# V_1.net
KiCad netlist of a schematic drawn in Altium Designer
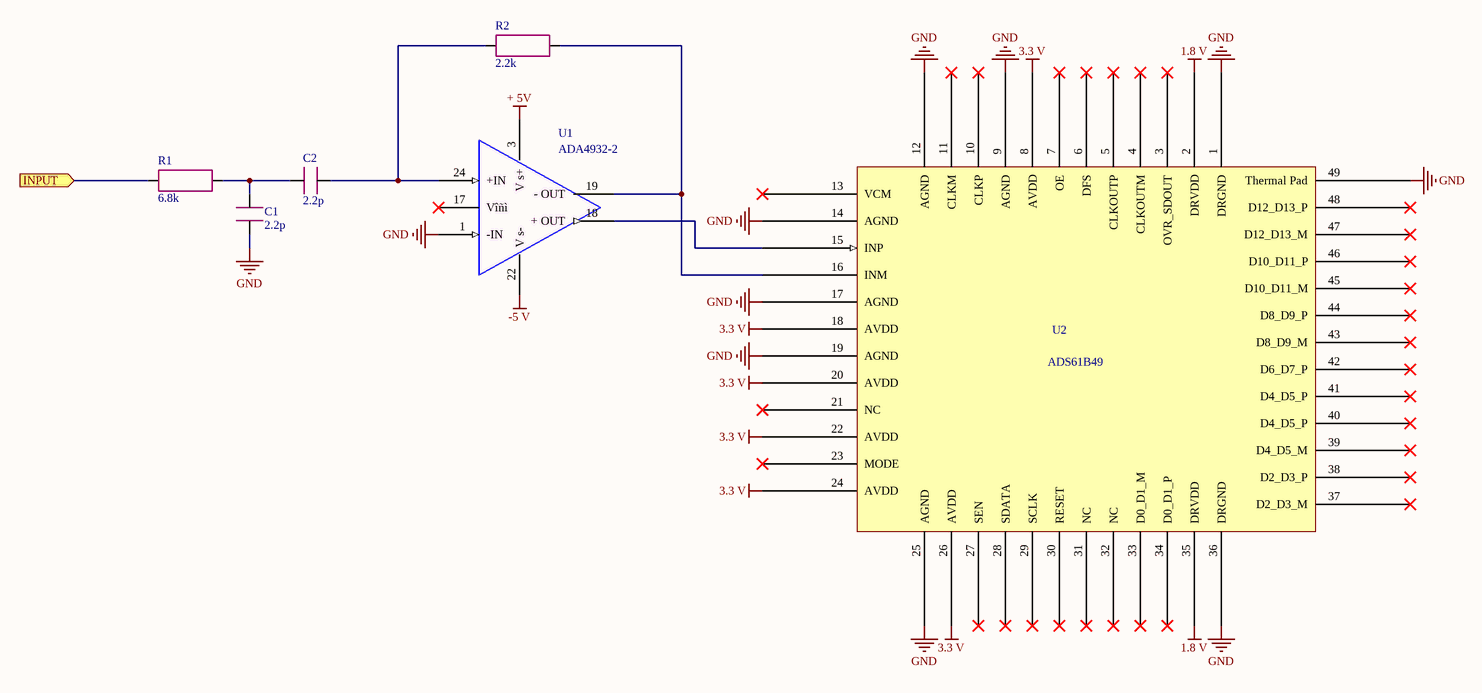
[diagram p0: V_1.SchDoc]

(export (version "E")
  (design (tool "Eeschema 10.0.6"))
  (components
    (comp (ref "C1") (value "2.2p") (footprint "V_1:C_0805") (libsource (lib "V_1") (part "C")))
    (comp (ref "C2") (value "2.2p") (footprint "V_1:C_0805") (libsource (lib "V_1") (part "C")))
    (comp (ref "R1") (value "6.8k") (footprint "V_1:R_0805") (libsource (lib "V_1") (part "R")))
    (comp (ref "R2") (value "2.2k") (footprint "V_1:R_0805") (libsource (lib "V_1") (part "R")))
    (comp (ref "U1")
      (value "ADA4932-2")
      (footprint "V_1:ADA4932-2")
      (libsource (lib "V_1") (part "ADA4932-2"))
    )
    (comp (ref "U2") (value "ADS61B49") (footprint "V_1:ADS61B49") (libsource (lib "V_1") (part "ADS61B49")))
  )
  (nets
    (net (code "1") (name "+ 5V") (class "Default")
      (node (ref "U1") (pin "3") (pinfunction "V_s+_3") (pintype "power_in"))
    )
    (net (code "2") (name "-5 V") (class "Default")
      (node (ref "U1") (pin "22") (pinfunction "V_s-_22") (pintype "power_in"))
    )
    (net (code "3") (name "/INPUT") (class "Default")
      (node (ref "R1") (pin "1") (pinfunction "1_1") (pintype "passive"))
    )
    (net (code "4") (name "1.8 V") (class "Default")
      (node (ref "U2") (pin "2") (pinfunction "DRVDD_2") (pintype "power_in"))
      (node (ref "U2") (pin "35") (pinfunction "DRVDD_35") (pintype "power_in"))
    )
    (net (code "5") (name "3.3 V") (class "Default")
      (node (ref "U2") (pin "18") (pinfunction "AVDD_18") (pintype "power_in"))
      (node (ref "U2") (pin "20") (pinfunction "AVDD_20") (pintype "power_in"))
      (node (ref "U2") (pin "22") (pinfunction "AVDD_22") (pintype "power_in"))
      (node (ref "U2") (pin "24") (pinfunction "AVDD_24") (pintype "power_in"))
      (node (ref "U2") (pin "26") (pinfunction "AVDD_26") (pintype "power_in"))
      (node (ref "U2") (pin "8") (pinfunction "AVDD_8") (pintype "power_in"))
    )
    (net (code "6") (name "GND") (class "Default")
      (node (ref "C1") (pin "1") (pinfunction "1_1") (pintype "power_in"))
      (node (ref "U1") (pin "1") (pinfunction "-IN_1") (pintype "input"))
      (node (ref "U2") (pin "1") (pinfunction "DRGND_1") (pintype "power_in"))
      (node (ref "U2") (pin "12") (pinfunction "AGND_12") (pintype "power_in"))
      (node (ref "U2") (pin "14") (pinfunction "AGND_14") (pintype "power_in"))
      (node (ref "U2") (pin "17") (pinfunction "AGND_17") (pintype "power_in"))
      (node (ref "U2") (pin "19") (pinfunction "AGND_19") (pintype "power_in"))
      (node (ref "U2") (pin "25") (pinfunction "AGND_25") (pintype "power_in"))
      (node (ref "U2") (pin "36") (pinfunction "DRGND_36") (pintype "power_in"))
      (node (ref "U2") (pin "49") (pinfunction "Thermal_Pad_49") (pintype "power_in"))
      (node (ref "U2") (pin "9") (pinfunction "AGND_9") (pintype "power_in"))
    )
    (net (code "7") (name "Net-(C1-Pad2)") (class "Default")
      (node (ref "C1") (pin "2") (pinfunction "2_2") (pintype "power_in"))
      (node (ref "C2") (pin "1") (pinfunction "1_1") (pintype "power_in"))
      (node (ref "R1") (pin "2") (pinfunction "2_2") (pintype "passive"))
    )
    (net (code "8") (name "Net-(U1-+IN)") (class "Default")
      (node (ref "C2") (pin "2") (pinfunction "2_2") (pintype "power_in"))
      (node (ref "R2") (pin "1") (pinfunction "1_1") (pintype "passive"))
      (node (ref "U1") (pin "24") (pinfunction "+IN_24") (pintype "input"))
    )
    (net (code "9") (name "Net-(U1-+_OUT)") (class "Default")
      (node (ref "U1") (pin "18") (pinfunction "+_OUT_18") (pintype "output"))
      (node (ref "U2") (pin "15") (pinfunction "INP_15") (pintype "input"))
    )
    (net (code "10") (name "Net-(U1--_OUT)") (class "Default")
      (node (ref "R2") (pin "2") (pinfunction "2_2") (pintype "passive"))
      (node (ref "U1") (pin "19") (pinfunction "-_OUT_19") (pintype "power_in"))
      (node (ref "U2") (pin "16") (pinfunction "INM_16") (pintype "power_in"))
    )
    (net (code "11") (name "unconnected-(U1-Vîñì-Pad17)") (class "Default")
      (node (ref "U1") (pin "17") (pinfunction "Vîñì_17") (pintype "power_in+no_connect"))
    )
    (net (code "12") (name "unconnected-(U2-CLKM-Pad11)") (class "Default")
      (node (ref "U2") (pin "11") (pinfunction "CLKM_11") (pintype "passive+no_connect"))
    )
    (net (code "13") (name "unconnected-(U2-CLKOUTM-Pad4)") (class "Default")
      (node (ref "U2") (pin "4") (pinfunction "CLKOUTM_4") (pintype "passive+no_connect"))
    )
    (net (code "14") (name "unconnected-(U2-CLKOUTP-Pad5)") (class "Default")
      (node (ref "U2") (pin "5") (pinfunction "CLKOUTP_5") (pintype "passive+no_connect"))
    )
    (net (code "15") (name "unconnected-(U2-CLKP-Pad10)") (class "Default")
      (node (ref "U2") (pin "10") (pinfunction "CLKP_10") (pintype "passive+no_connect"))
    )
    (net (code "16") (name "unconnected-(U2-D0_D1_M-Pad33)") (class "Default")
      (node (ref "U2") (pin "33") (pinfunction "D0_D1_M_33") (pintype "passive+no_connect"))
    )
    (net (code "17") (name "unconnected-(U2-D0_D1_P-Pad34)") (class "Default")
      (node (ref "U2") (pin "34") (pinfunction "D0_D1_P_34") (pintype "passive+no_connect"))
    )
    (net (code "18") (name "unconnected-(U2-D2_D3_M-Pad37)") (class "Default")
      (node (ref "U2") (pin "37") (pinfunction "D2_D3_M_37") (pintype "passive+no_connect"))
    )
    (net (code "19") (name "unconnected-(U2-D2_D3_P-Pad38)") (class "Default")
      (node (ref "U2") (pin "38") (pinfunction "D2_D3_P_38") (pintype "passive+no_connect"))
    )
    (net (code "20") (name "unconnected-(U2-D4_D5_M-Pad39)") (class "Default")
      (node (ref "U2") (pin "39") (pinfunction "D4_D5_M_39") (pintype "passive+no_connect"))
    )
    (net (code "21") (name "unconnected-(U2-D4_D5_P-Pad40)") (class "Default")
      (node (ref "U2") (pin "40") (pinfunction "D4_D5_P_40") (pintype "passive+no_connect"))
    )
    (net (code "22") (name "unconnected-(U2-D4_D5_P-Pad41)") (class "Default")
      (node (ref "U2") (pin "41") (pinfunction "D4_D5_P_41") (pintype "passive+no_connect"))
    )
    (net (code "23") (name "unconnected-(U2-D6_D7_P-Pad42)") (class "Default")
      (node (ref "U2") (pin "42") (pinfunction "D6_D7_P_42") (pintype "passive+no_connect"))
    )
    (net (code "24") (name "unconnected-(U2-D8_D9_M-Pad43)") (class "Default")
      (node (ref "U2") (pin "43") (pinfunction "D8_D9_M_43") (pintype "passive+no_connect"))
    )
    (net (code "25") (name "unconnected-(U2-D8_D9_P-Pad44)") (class "Default")
      (node (ref "U2") (pin "44") (pinfunction "D8_D9_P_44") (pintype "passive+no_connect"))
    )
    (net (code "26") (name "unconnected-(U2-D10_D11_M-Pad45)") (class "Default")
      (node (ref "U2") (pin "45") (pinfunction "D10_D11_M_45") (pintype "passive+no_connect"))
    )
    (net (code "27") (name "unconnected-(U2-D10_D11_P-Pad46)") (class "Default")
      (node (ref "U2") (pin "46") (pinfunction "D10_D11_P_46") (pintype "passive+no_connect"))
    )
    (net (code "28") (name "unconnected-(U2-D12_D13_M-Pad47)") (class "Default")
      (node (ref "U2") (pin "47") (pinfunction "D12_D13_M_47") (pintype "passive+no_connect"))
    )
    (net (code "29") (name "unconnected-(U2-D12_D13_P-Pad48)") (class "Default")
      (node (ref "U2") (pin "48") (pinfunction "D12_D13_P_48") (pintype "passive+no_connect"))
    )
    (net (code "30") (name "unconnected-(U2-DFS-Pad6)") (class "Default")
      (node (ref "U2") (pin "6") (pinfunction "DFS_6") (pintype "passive+no_connect"))
    )
    (net (code "31") (name "unconnected-(U2-MODE-Pad23)") (class "Default")
      (node (ref "U2") (pin "23") (pinfunction "MODE_23") (pintype "passive+no_connect"))
    )
    (net (code "32") (name "unconnected-(U2-NC-Pad21)") (class "Default")
      (node (ref "U2") (pin "21") (pinfunction "NC_21") (pintype "passive+no_connect"))
    )
    (net (code "33") (name "unconnected-(U2-NC-Pad31)") (class "Default")
      (node (ref "U2") (pin "31") (pinfunction "NC_31") (pintype "passive+no_connect"))
    )
    (net (code "34") (name "unconnected-(U2-NC-Pad32)") (class "Default")
      (node (ref "U2") (pin "32") (pinfunction "NC_32") (pintype "passive+no_connect"))
    )
    (net (code "35") (name "unconnected-(U2-OE-Pad7)") (class "Default")
      (node (ref "U2") (pin "7") (pinfunction "OE_7") (pintype "passive+no_connect"))
    )
    (net (code "36") (name "unconnected-(U2-OVR_SDOUT-Pad3)") (class "Default")
      (node (ref "U2") (pin "3") (pinfunction "OVR_SDOUT_3") (pintype "passive+no_connect"))
    )
    (net (code "37") (name "unconnected-(U2-RESET-Pad30)") (class "Default")
      (node (ref "U2") (pin "30") (pinfunction "RESET_30") (pintype "passive+no_connect"))
    )
    (net (code "38") (name "unconnected-(U2-SCLK-Pad29)") (class "Default")
      (node (ref "U2") (pin "29") (pinfunction "SCLK_29") (pintype "passive+no_connect"))
    )
    (net (code "39") (name "unconnected-(U2-SDATA-Pad28)") (class "Default")
      (node (ref "U2") (pin "28") (pinfunction "SDATA_28") (pintype "passive+no_connect"))
    )
    (net (code "40") (name "unconnected-(U2-SEN-Pad27)") (class "Default")
      (node (ref "U2") (pin "27") (pinfunction "SEN_27") (pintype "passive+no_connect"))
    )
    (net (code "41") (name "unconnected-(U2-VCM-Pad13)") (class "Default")
      (node (ref "U2") (pin "13") (pinfunction "VCM_13") (pintype "passive+no_connect"))
    )
  )
)
